# C-11_SOM_HDR.net
KiCad netlist of a schematic drawn in Altium Designer
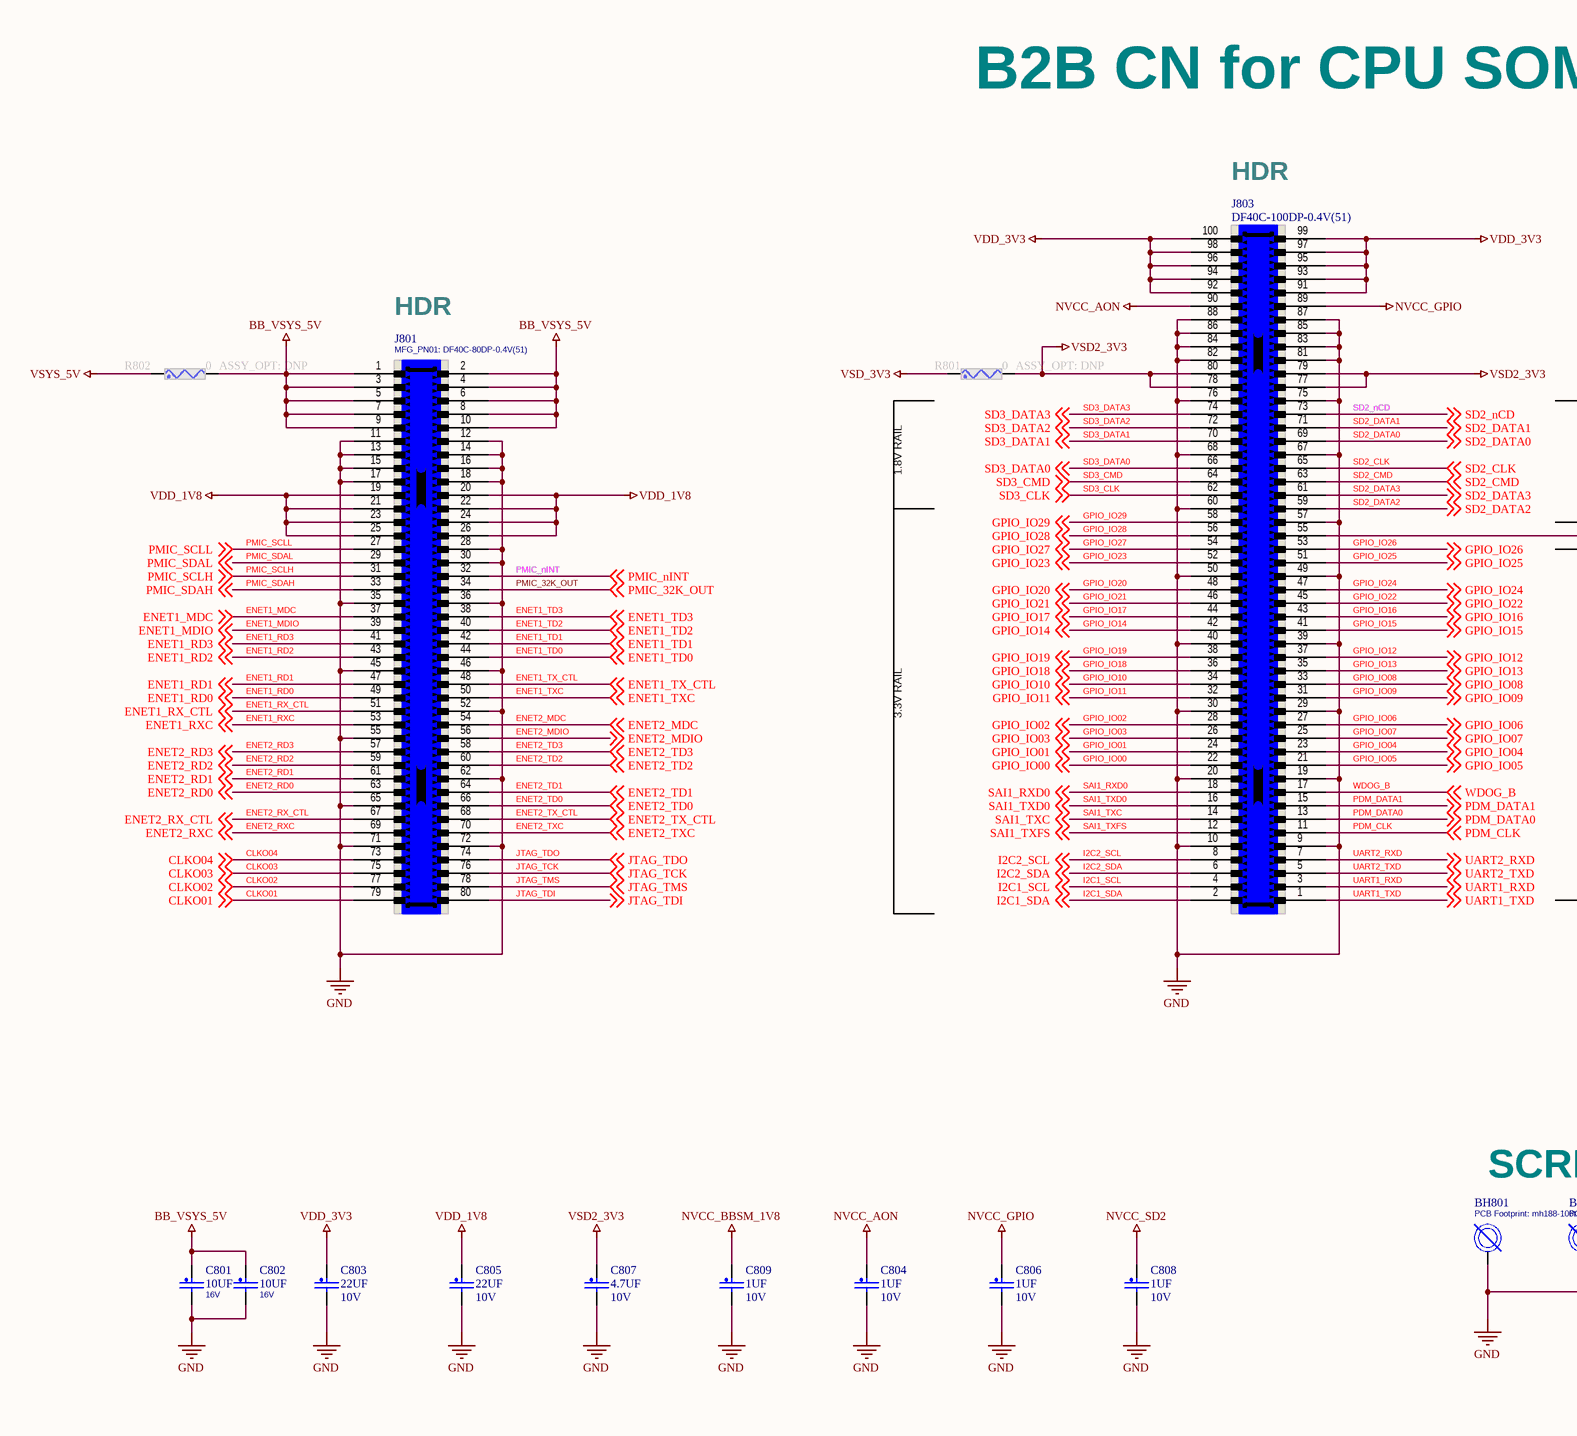
[diagram p0: C-11 SOM HDR.SchDoc, left]
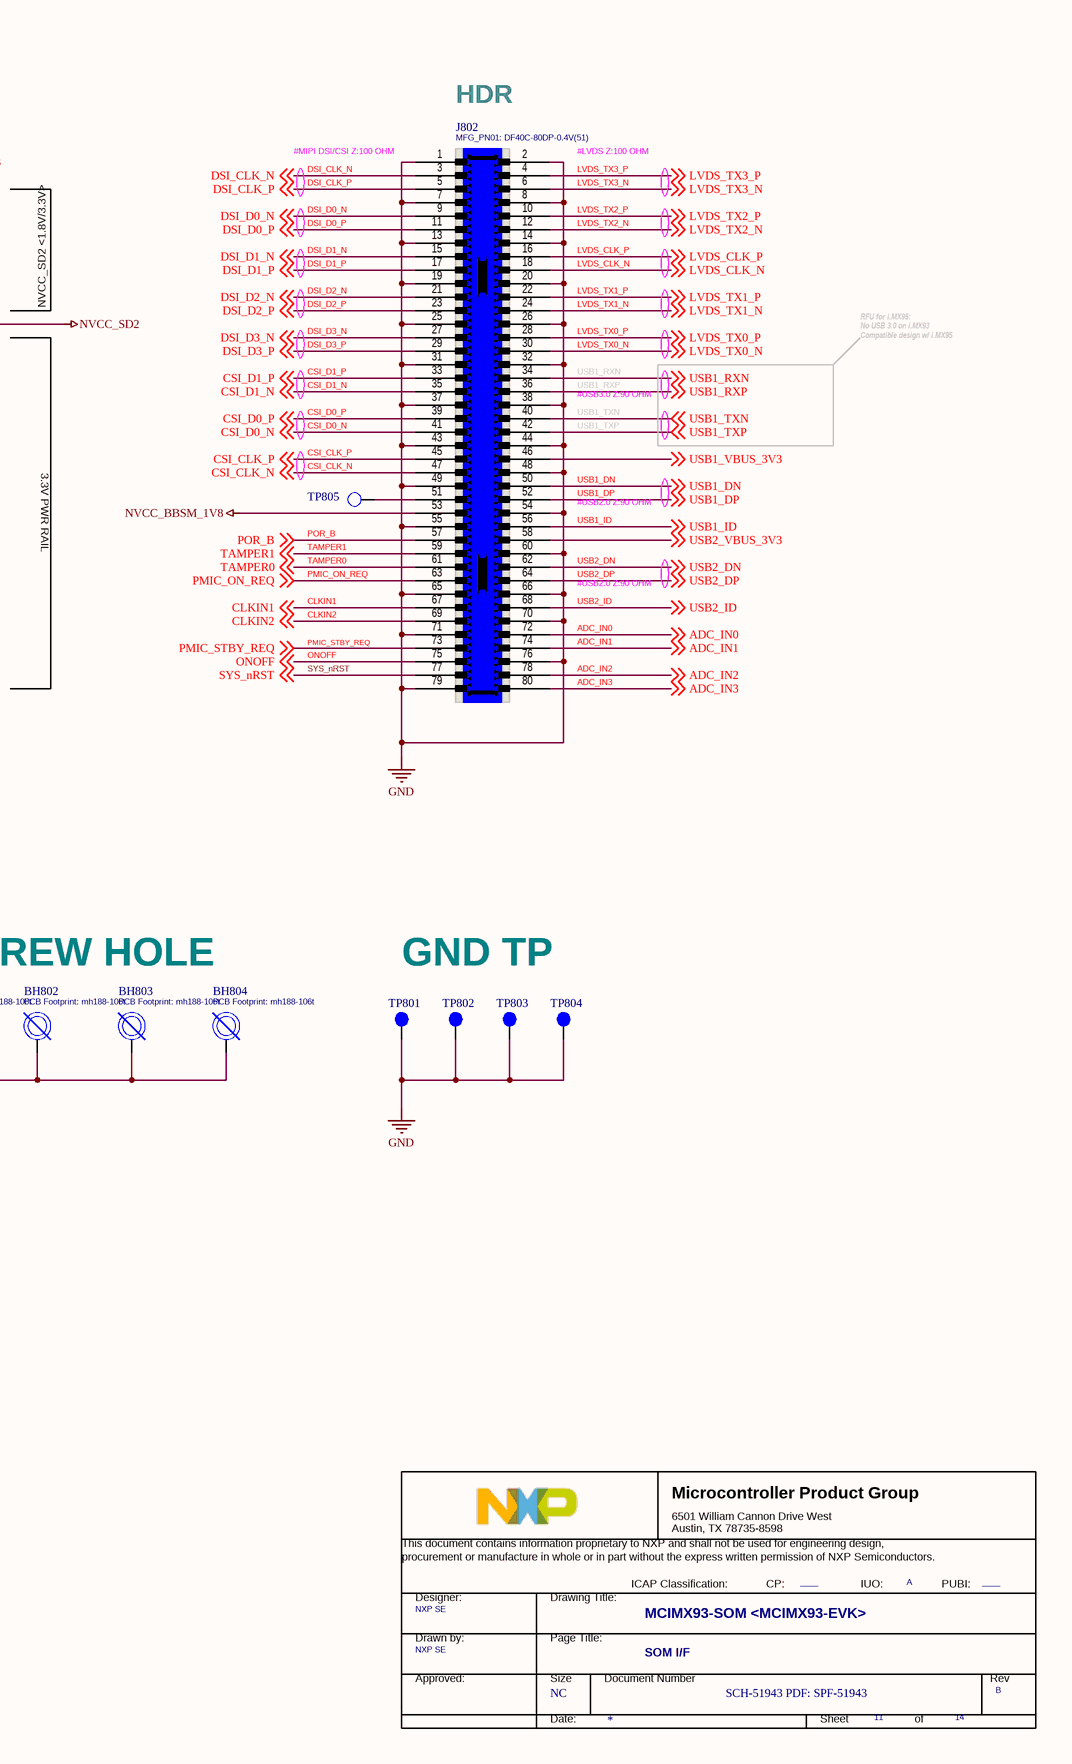
[diagram p1: C-11 SOM HDR.SchDoc, right]

(export (version "E")
  (design (tool "Eeschema 10.0.6"))
  (components
    (comp (ref "BH801")
      (value "FMC MOUNTING HOLE")
      (footprint "mh188-106t")
      (description "MOUNTING HOLE PLATED DRILL 2.7MM KEEPOUT R2.9MM TH, NO PART TO ORDER")
      (fields (field (name "PCB FOOTPRINT") "mh188-106t"))
      (libsource (lib "*") (part "MOUNT_HOLE"))
    )
    (comp (ref "BH802")
      (value "FMC MOUNTING HOLE")
      (footprint "mh188-106t")
      (description "MOUNTING HOLE PLATED DRILL 2.7MM KEEPOUT R2.9MM TH, NO PART TO ORDER")
      (fields (field (name "PCB FOOTPRINT") "mh188-106t"))
      (libsource (lib "*") (part "MOUNT_HOLE"))
    )
    (comp (ref "BH803")
      (value "FMC MOUNTING HOLE")
      (footprint "mh188-106t")
      (description "MOUNTING HOLE PLATED DRILL 2.7MM KEEPOUT R2.9MM TH, NO PART TO ORDER")
      (fields (field (name "PCB FOOTPRINT") "mh188-106t"))
      (libsource (lib "*") (part "MOUNT_HOLE"))
    )
    (comp (ref "BH804")
      (value "FMC MOUNTING HOLE")
      (footprint "mh188-106t")
      (description "MOUNTING HOLE PLATED DRILL 2.7MM KEEPOUT R2.9MM TH, NO PART TO ORDER")
      (fields (field (name "PCB FOOTPRINT") "mh188-106t"))
      (libsource (lib "*") (part "MOUNT_HOLE"))
    )
    (comp (ref "C801")
      (value "10UF")
      (footprint "CC0603")
      (description "CAP CER 10.0uF 16V 10% X5R 0603")
      (fields (field (name "TOLERANCE") "10%") (field (name "VOLTAGE") "16V"))
      (libsource (lib "*") (part "CAP_NP"))
    )
    (comp (ref "C802")
      (value "10UF")
      (footprint "CC0603")
      (description "CAP CER 10.0uF 16V 10% X5R 0603")
      (fields (field (name "VOLTAGE") "16V") (field (name "TOLERANCE") "10%"))
      (libsource (lib "*") (part "CAP_NP"))
    )
    (comp (ref "C803")
      (value "22UF")
      (footprint "CC0603")
      (description "CAP CER 22uF 10V 20% X5R 0603")
      (fields (field (name "TOLERANCE") "20%") (field (name "VOLTAGE") "10V"))
      (libsource (lib "*") (part "CAP_NP"))
    )
    (comp (ref "C804")
      (value "1UF")
      (footprint "0201_CC")
      (description "CAP CER 1.0uF 10V 10% X5R 0201")
      (fields (field (name "TOLERANCE") "10%") (field (name "VOLTAGE") "10V"))
      (libsource (lib "*") (part "CAP_NP"))
    )
    (comp (ref "C805")
      (value "22UF")
      (footprint "CC0603")
      (description "CAP CER 22uF 10V 20% X5R 0603")
      (fields (field (name "TOLERANCE") "20%") (field (name "VOLTAGE") "10V"))
      (libsource (lib "*") (part "CAP_NP"))
    )
    (comp (ref "C806")
      (value "1UF")
      (footprint "0201_CC")
      (description "CAP CER 1.0uF 10V 10% X5R 0201")
      (fields (field (name "TOLERANCE") "10%") (field (name "VOLTAGE") "10V"))
      (libsource (lib "*") (part "CAP_NP"))
    )
    (comp (ref "C807")
      (value "4.7UF")
      (footprint "cc0402_tol0p15")
      (description "CAP CER 4.7uF 10V 10% X5R 0402")
      (fields (field (name "VOLTAGE") "10V") (field (name "TOLERANCE") "10%"))
      (libsource (lib "*") (part "CAP_NP"))
    )
    (comp (ref "C808")
      (value "1UF")
      (footprint "0201_CC")
      (description "CAP CER 1.0uF 10V 10% X5R 0201")
      (fields (field (name "VOLTAGE") "10V") (field (name "TOLERANCE") "10%"))
      (libsource (lib "*") (part "CAP_NP"))
    )
    (comp (ref "C809")
      (value "1UF")
      (footprint "0201_CC")
      (description "CAP CER 1.0uF 10V 10% X5R 0201")
      (fields (field (name "TOLERANCE") "10%") (field (name "VOLTAGE") "10V"))
      (libsource (lib "*") (part "CAP_NP"))
    )
    (comp (ref "J801")
      (value "CON 2X40")
      (footprint "con80_0p4_17p7x2p05_sm")
      (description "CON 2X40 PLUG SHRD SMT 0.4MM SP 51H AU")
      (fields (field (name "MFG_PN01") "DF40C-80DP-0.4V(51)"))
      (libsource (lib "*") (part "CON_2X40_A"))
    )
    (comp (ref "J802")
      (value "CON 2X40")
      (footprint "con80_0p4_17p7x2p05_sm")
      (description "CON 2X40 PLUG SHRD SMT 0.4MM SP 51H AU")
      (fields (field (name "MFG_PN01") "DF40C-80DP-0.4V(51)"))
      (libsource (lib "*") (part "CON_2X40_A"))
    )
    (comp (ref "J803")
      (value "DF40C-100DP-0.4V(51)")
      (footprint "con100_0p4_21p7x2p05_sm")
      (description "CON 2X50 PLUG SHRD SMT 0.4MM SP 51H AU")
      (libsource (lib "*") (part "HDR_2X50_M_A"))
    )
    (comp (ref "R801")
      (value "0")
      (footprint "0603_CC")
      (description "RES MF ZERO OHM 1/10W -- 0603")
      (fields (field (name "ASSY_OPT") "DNP"))
      (libsource (lib "*") (part "RES"))
    )
    (comp (ref "R802")
      (value "0")
      (footprint "RC0805_OV")
      (description "RES MF ZERO OHM 1/8W -- 0805")
      (fields (field (name "ASSY_OPT") "DNP") (field (name "TOLERANCE") "5%"))
      (libsource (lib "*") (part "RES"))
    )
    (comp (ref "TP801")
      (value "TPAD_050")
      (footprint "TPAD_050")
      (description "TEST POINT PAD 50MIL DIA SMT, NO PART TO ORDER")
      (libsource (lib "*") (part "TESTLOOP"))
    )
    (comp (ref "TP802")
      (value "TPAD_050")
      (footprint "TPAD_050")
      (description "TEST POINT PAD 50MIL DIA SMT, NO PART TO ORDER")
      (libsource (lib "*") (part "TESTLOOP"))
    )
    (comp (ref "TP803")
      (value "TPAD_050")
      (footprint "TPAD_050")
      (description "TEST POINT PAD 50MIL DIA SMT, NO PART TO ORDER")
      (libsource (lib "*") (part "TESTLOOP"))
    )
    (comp (ref "TP804")
      (value "TPAD_050")
      (footprint "TPAD_050")
      (description "TEST POINT PAD 50MIL DIA SMT, NO PART TO ORDER")
      (libsource (lib "*") (part "TESTLOOP"))
    )
    (comp (ref "TP805")
      (value "TP_35MIL")
      (footprint "testpoint_35mil")
      (description "TEST POINT PAD .035 SMT, no part to order")
      (libsource (lib "*") (part "T POINT R"))
    )
  )
  (nets
    (net (code "1") (name "ADC_IN0") (class "Default")
      (node (ref "J802") (pin "72") (pinfunction "B36_72") (pintype "passive"))
    )
    (net (code "2") (name "ADC_IN1") (class "Default")
      (node (ref "J802") (pin "74") (pinfunction "B37_74") (pintype "passive"))
    )
    (net (code "3") (name "ADC_IN2") (class "Default")
      (node (ref "J802") (pin "78") (pinfunction "B39_78") (pintype "passive"))
    )
    (net (code "4") (name "ADC_IN3") (class "Default")
      (node (ref "J802") (pin "80") (pinfunction "B40_80") (pintype "passive"))
    )
    (net (code "5") (name "BB_VSYS_5V") (class "Default")
      (node (ref "C801") (pin "1") (pinfunction "1_1") (pintype "passive"))
      (node (ref "C802") (pin "1") (pinfunction "1_1") (pintype "passive"))
      (node (ref "J801") (pin "1") (pinfunction "A1_1") (pintype "passive"))
      (node (ref "J801") (pin "10") (pinfunction "B5_10") (pintype "passive"))
      (node (ref "J801") (pin "2") (pinfunction "B1_2") (pintype "passive"))
      (node (ref "J801") (pin "3") (pinfunction "A2_3") (pintype "passive"))
      (node (ref "J801") (pin "4") (pinfunction "B2_4") (pintype "passive"))
      (node (ref "J801") (pin "5") (pinfunction "A3_5") (pintype "passive"))
      (node (ref "J801") (pin "6") (pinfunction "B3_6") (pintype "passive"))
      (node (ref "J801") (pin "7") (pinfunction "A4_7") (pintype "passive"))
      (node (ref "J801") (pin "8") (pinfunction "B4_8") (pintype "passive"))
      (node (ref "J801") (pin "9") (pinfunction "A5_9") (pintype "passive"))
      (node (ref "R802") (pin "2") (pinfunction "2_2") (pintype "passive"))
    )
    (net (code "6") (name "CLKIN1") (class "Default")
      (node (ref "J802") (pin "67") (pinfunction "A34_67") (pintype "passive"))
    )
    (net (code "7") (name "CLKIN2") (class "Default")
      (node (ref "J802") (pin "69") (pinfunction "A35_69") (pintype "passive"))
    )
    (net (code "8") (name "CLKO01") (class "Default")
      (node (ref "J801") (pin "79") (pinfunction "A40_79") (pintype "passive"))
    )
    (net (code "9") (name "CLKO02") (class "Default")
      (node (ref "J801") (pin "77") (pinfunction "A39_77") (pintype "passive"))
    )
    (net (code "10") (name "CLKO03") (class "Default")
      (node (ref "J801") (pin "75") (pinfunction "A38_75") (pintype "passive"))
    )
    (net (code "11") (name "CLKO04") (class "Default")
      (node (ref "J801") (pin "73") (pinfunction "A37_73") (pintype "passive"))
    )
    (net (code "12") (name "CSI_CLK_N") (class "Default")
      (node (ref "J802") (pin "47") (pinfunction "A24_47") (pintype "passive"))
    )
    (net (code "13") (name "CSI_CLK_P") (class "Default")
      (node (ref "J802") (pin "45") (pinfunction "A23_45") (pintype "passive"))
    )
    (net (code "14") (name "CSI_D0_N") (class "Default")
      (node (ref "J802") (pin "41") (pinfunction "A21_41") (pintype "passive"))
    )
    (net (code "15") (name "CSI_D0_P") (class "Default")
      (node (ref "J802") (pin "39") (pinfunction "A20_39") (pintype "passive"))
    )
    (net (code "16") (name "CSI_D1_N") (class "Default")
      (node (ref "J802") (pin "35") (pinfunction "A18_35") (pintype "passive"))
    )
    (net (code "17") (name "CSI_D1_P") (class "Default")
      (node (ref "J802") (pin "33") (pinfunction "A17_33") (pintype "passive"))
    )
    (net (code "18") (name "DSI_CLK_N") (class "Default")
      (node (ref "J802") (pin "3") (pinfunction "A2_3") (pintype "passive"))
    )
    (net (code "19") (name "DSI_CLK_P") (class "Default")
      (node (ref "J802") (pin "5") (pinfunction "A3_5") (pintype "passive"))
    )
    (net (code "20") (name "DSI_D0_N") (class "Default")
      (node (ref "J802") (pin "9") (pinfunction "A5_9") (pintype "passive"))
    )
    (net (code "21") (name "DSI_D0_P") (class "Default")
      (node (ref "J802") (pin "11") (pinfunction "A6_11") (pintype "passive"))
    )
    (net (code "22") (name "DSI_D1_N") (class "Default")
      (node (ref "J802") (pin "15") (pinfunction "A8_15") (pintype "passive"))
    )
    (net (code "23") (name "DSI_D1_P") (class "Default")
      (node (ref "J802") (pin "17") (pinfunction "A9_17") (pintype "passive"))
    )
    (net (code "24") (name "DSI_D2_N") (class "Default")
      (node (ref "J802") (pin "21") (pinfunction "A11_21") (pintype "passive"))
    )
    (net (code "25") (name "DSI_D2_P") (class "Default")
      (node (ref "J802") (pin "23") (pinfunction "A12_23") (pintype "passive"))
    )
    (net (code "26") (name "DSI_D3_N") (class "Default")
      (node (ref "J802") (pin "27") (pinfunction "A14_27") (pintype "passive"))
    )
    (net (code "27") (name "DSI_D3_P") (class "Default")
      (node (ref "J802") (pin "29") (pinfunction "A15_29") (pintype "passive"))
    )
    (net (code "28") (name "ENET1_MDC") (class "Default")
      (node (ref "J801") (pin "37") (pinfunction "A19_37") (pintype "passive"))
    )
    (net (code "29") (name "ENET1_MDIO") (class "Default")
      (node (ref "J801") (pin "39") (pinfunction "A20_39") (pintype "passive"))
    )
    (net (code "30") (name "ENET1_RD0") (class "Default")
      (node (ref "J801") (pin "49") (pinfunction "A25_49") (pintype "passive"))
    )
    (net (code "31") (name "ENET1_RD1") (class "Default")
      (node (ref "J801") (pin "47") (pinfunction "A24_47") (pintype "passive"))
    )
    (net (code "32") (name "ENET1_RD2") (class "Default")
      (node (ref "J801") (pin "43") (pinfunction "A22_43") (pintype "passive"))
    )
    (net (code "33") (name "ENET1_RD3") (class "Default")
      (node (ref "J801") (pin "41") (pinfunction "A21_41") (pintype "passive"))
    )
    (net (code "34") (name "ENET1_RXC") (class "Default")
      (node (ref "J801") (pin "53") (pinfunction "A27_53") (pintype "passive"))
    )
    (net (code "35") (name "ENET1_RX_CTL") (class "Default")
      (node (ref "J801") (pin "51") (pinfunction "A26_51") (pintype "passive"))
    )
    (net (code "36") (name "ENET1_TD0") (class "Default")
      (node (ref "J801") (pin "44") (pinfunction "B22_44") (pintype "passive"))
    )
    (net (code "37") (name "ENET1_TD1") (class "Default")
      (node (ref "J801") (pin "42") (pinfunction "B21_42") (pintype "passive"))
    )
    (net (code "38") (name "ENET1_TD2") (class "Default")
      (node (ref "J801") (pin "40") (pinfunction "B20_40") (pintype "passive"))
    )
    (net (code "39") (name "ENET1_TD3") (class "Default")
      (node (ref "J801") (pin "38") (pinfunction "B19_38") (pintype "passive"))
    )
    (net (code "40") (name "ENET1_TXC") (class "Default")
      (node (ref "J801") (pin "50") (pinfunction "B25_50") (pintype "passive"))
    )
    (net (code "41") (name "ENET1_TX_CTL") (class "Default")
      (node (ref "J801") (pin "48") (pinfunction "B24_48") (pintype "passive"))
    )
    (net (code "42") (name "ENET2_MDC") (class "Default")
      (node (ref "J801") (pin "54") (pinfunction "B27_54") (pintype "passive"))
    )
    (net (code "43") (name "ENET2_MDIO") (class "Default")
      (node (ref "J801") (pin "56") (pinfunction "B28_56") (pintype "passive"))
    )
    (net (code "44") (name "ENET2_RD0") (class "Default")
      (node (ref "J801") (pin "63") (pinfunction "A32_63") (pintype "passive"))
    )
    (net (code "45") (name "ENET2_RD1") (class "Default")
      (node (ref "J801") (pin "61") (pinfunction "A31_61") (pintype "passive"))
    )
    (net (code "46") (name "ENET2_RD2") (class "Default")
      (node (ref "J801") (pin "59") (pinfunction "A30_59") (pintype "passive"))
    )
    (net (code "47") (name "ENET2_RD3") (class "Default")
      (node (ref "J801") (pin "57") (pinfunction "A29_57") (pintype "passive"))
    )
    (net (code "48") (name "ENET2_RXC") (class "Default")
      (node (ref "J801") (pin "69") (pinfunction "A35_69") (pintype "passive"))
    )
    (net (code "49") (name "ENET2_RX_CTL") (class "Default")
      (node (ref "J801") (pin "67") (pinfunction "A34_67") (pintype "passive"))
    )
    (net (code "50") (name "ENET2_TD0") (class "Default")
      (node (ref "J801") (pin "66") (pinfunction "B33_66") (pintype "passive"))
    )
    (net (code "51") (name "ENET2_TD1") (class "Default")
      (node (ref "J801") (pin "64") (pinfunction "B32_64") (pintype "passive"))
    )
    (net (code "52") (name "ENET2_TD2") (class "Default")
      (node (ref "J801") (pin "60") (pinfunction "B30_60") (pintype "passive"))
    )
    (net (code "53") (name "ENET2_TD3") (class "Default")
      (node (ref "J801") (pin "58") (pinfunction "B29_58") (pintype "passive"))
    )
    (net (code "54") (name "ENET2_TXC") (class "Default")
      (node (ref "J801") (pin "70") (pinfunction "B35_70") (pintype "passive"))
    )
    (net (code "55") (name "ENET2_TX_CTL") (class "Default")
      (node (ref "J801") (pin "68") (pinfunction "B34_68") (pintype "passive"))
    )
    (net (code "56") (name "GND") (class "Default")
      (node (ref "BH801") (pin "1") (pinfunction "1_1") (pintype "passive"))
      (node (ref "BH802") (pin "1") (pinfunction "1_1") (pintype "passive"))
      (node (ref "BH803") (pin "1") (pinfunction "1_1") (pintype "passive"))
      (node (ref "BH804") (pin "1") (pinfunction "1_1") (pintype "passive"))
      (node (ref "C801") (pin "2") (pinfunction "2_2") (pintype "passive"))
      (node (ref "C802") (pin "2") (pinfunction "2_2") (pintype "passive"))
      (node (ref "C803") (pin "2") (pinfunction "2_2") (pintype "passive"))
      (node (ref "C804") (pin "2") (pinfunction "2_2") (pintype "passive"))
      (node (ref "C805") (pin "2") (pinfunction "2_2") (pintype "passive"))
      (node (ref "C806") (pin "2") (pinfunction "2_2") (pintype "passive"))
      (node (ref "C807") (pin "2") (pinfunction "2_2") (pintype "passive"))
      (node (ref "C808") (pin "2") (pinfunction "2_2") (pintype "passive"))
      (node (ref "C809") (pin "2") (pinfunction "2_2") (pintype "passive"))
      (node (ref "J801") (pin "11") (pinfunction "A6_11") (pintype "passive"))
      (node (ref "J801") (pin "12") (pinfunction "B6_12") (pintype "passive"))
      (node (ref "J801") (pin "13") (pinfunction "A7_13") (pintype "passive"))
      (node (ref "J801") (pin "14") (pinfunction "B7_14") (pintype "passive"))
      (node (ref "J801") (pin "15") (pinfunction "A8_15") (pintype "passive"))
      (node (ref "J801") (pin "16") (pinfunction "B8_16") (pintype "passive"))
      (node (ref "J801") (pin "17") (pinfunction "A9_17") (pintype "passive"))
      (node (ref "J801") (pin "18") (pinfunction "B9_18") (pintype "passive"))
      (node (ref "J801") (pin "28") (pinfunction "B14_28") (pintype "passive"))
      (node (ref "J801") (pin "30") (pinfunction "B15_30") (pintype "passive"))
      (node (ref "J801") (pin "35") (pinfunction "A18_35") (pintype "passive"))
      (node (ref "J801") (pin "36") (pinfunction "B18_36") (pintype "passive"))
      (node (ref "J801") (pin "45") (pinfunction "A23_45") (pintype "passive"))
      (node (ref "J801") (pin "46") (pinfunction "B23_46") (pintype "passive"))
      (node (ref "J801") (pin "52") (pinfunction "B26_52") (pintype "passive"))
      (node (ref "J801") (pin "55") (pinfunction "A28_55") (pintype "passive"))
      (node (ref "J801") (pin "62") (pinfunction "B31_62") (pintype "passive"))
      (node (ref "J801") (pin "65") (pinfunction "A33_65") (pintype "passive"))
      (node (ref "J801") (pin "71") (pinfunction "A36_71") (pintype "passive"))
      (node (ref "J801") (pin "72") (pinfunction "B36_72") (pintype "passive"))
      (node (ref "J802") (pin "1") (pinfunction "A1_1") (pintype "passive"))
      (node (ref "J802") (pin "13") (pinfunction "A7_13") (pintype "passive"))
      (node (ref "J802") (pin "14") (pinfunction "B7_14") (pintype "passive"))
      (node (ref "J802") (pin "19") (pinfunction "A10_19") (pintype "passive"))
      (node (ref "J802") (pin "2") (pinfunction "B1_2") (pintype "passive"))
      (node (ref "J802") (pin "20") (pinfunction "B10_20") (pintype "passive"))
      (node (ref "J802") (pin "25") (pinfunction "A13_25") (pintype "passive"))
      (node (ref "J802") (pin "26") (pinfunction "B13_26") (pintype "passive"))
      (node (ref "J802") (pin "31") (pinfunction "A16_31") (pintype "passive"))
      (node (ref "J802") (pin "32") (pinfunction "B16_32") (pintype "passive"))
      (node (ref "J802") (pin "37") (pinfunction "A19_37") (pintype "passive"))
      (node (ref "J802") (pin "38") (pinfunction "B19_38") (pintype "passive"))
      (node (ref "J802") (pin "43") (pinfunction "A22_43") (pintype "passive"))
      (node (ref "J802") (pin "44") (pinfunction "B22_44") (pintype "passive"))
      (node (ref "J802") (pin "48") (pinfunction "B24_48") (pintype "passive"))
      (node (ref "J802") (pin "49") (pinfunction "A25_49") (pintype "passive"))
      (node (ref "J802") (pin "54") (pinfunction "B27_54") (pintype "passive"))
      (node (ref "J802") (pin "55") (pinfunction "A28_55") (pintype "passive"))
      (node (ref "J802") (pin "60") (pinfunction "B30_60") (pintype "passive"))
      (node (ref "J802") (pin "65") (pinfunction "A33_65") (pintype "passive"))
      (node (ref "J802") (pin "66") (pinfunction "B33_66") (pintype "passive"))
      (node (ref "J802") (pin "7") (pinfunction "A4_7") (pintype "passive"))
      (node (ref "J802") (pin "70") (pinfunction "B35_70") (pintype "passive"))
      (node (ref "J802") (pin "71") (pinfunction "A36_71") (pintype "passive"))
      (node (ref "J802") (pin "76") (pinfunction "B38_76") (pintype "passive"))
      (node (ref "J802") (pin "79") (pinfunction "A40_79") (pintype "passive"))
      (node (ref "J802") (pin "8") (pinfunction "B4_8") (pintype "passive"))
      (node (ref "J803") (pin "10") (pinfunction "10_10") (pintype "passive"))
      (node (ref "J803") (pin "19") (pinfunction "19_19") (pintype "passive"))
      (node (ref "J803") (pin "20") (pinfunction "20_20") (pintype "passive"))
      (node (ref "J803") (pin "29") (pinfunction "29_29") (pintype "passive"))
      (node (ref "J803") (pin "30") (pinfunction "30_30") (pintype "passive"))
      (node (ref "J803") (pin "39") (pinfunction "39_39") (pintype "passive"))
      (node (ref "J803") (pin "40") (pinfunction "40_40") (pintype "passive"))
      (node (ref "J803") (pin "49") (pinfunction "49_49") (pintype "passive"))
      (node (ref "J803") (pin "50") (pinfunction "50_50") (pintype "passive"))
      (node (ref "J803") (pin "57") (pinfunction "57_57") (pintype "passive"))
      (node (ref "J803") (pin "60") (pinfunction "60_60") (pintype "passive"))
      (node (ref "J803") (pin "67") (pinfunction "67_67") (pintype "passive"))
      (node (ref "J803") (pin "68") (pinfunction "68_68") (pintype "passive"))
      (node (ref "J803") (pin "75") (pinfunction "75_75") (pintype "passive"))
      (node (ref "J803") (pin "76") (pinfunction "76_76") (pintype "passive"))
      (node (ref "J803") (pin "81") (pinfunction "81_81") (pintype "passive"))
      (node (ref "J803") (pin "82") (pinfunction "82_82") (pintype "passive"))
      (node (ref "J803") (pin "83") (pinfunction "83_83") (pintype "passive"))
      (node (ref "J803") (pin "84") (pinfunction "84_84") (pintype "passive"))
      (node (ref "J803") (pin "85") (pinfunction "85_85") (pintype "passive"))
      (node (ref "J803") (pin "86") (pinfunction "86_86") (pintype "passive"))
      (node (ref "J803") (pin "87") (pinfunction "87_87") (pintype "passive"))
      (node (ref "J803") (pin "88") (pinfunction "88_88") (pintype "passive"))
      (node (ref "J803") (pin "9") (pinfunction "9_9") (pintype "passive"))
      (node (ref "TP801") (pin "1") (pinfunction "Pin1_1") (pintype "passive"))
      (node (ref "TP802") (pin "1") (pinfunction "Pin1_1") (pintype "passive"))
      (node (ref "TP803") (pin "1") (pinfunction "Pin1_1") (pintype "passive"))
      (node (ref "TP804") (pin "1") (pinfunction "Pin1_1") (pintype "passive"))
    )
    (net (code "57") (name "GPIO_IO00") (class "Default")
      (node (ref "J803") (pin "22") (pinfunction "22_22") (pintype "passive"))
    )
    (net (code "58") (name "GPIO_IO01") (class "Default")
      (node (ref "J803") (pin "24") (pinfunction "24_24") (pintype "passive"))
    )
    (net (code "59") (name "GPIO_IO02") (class "Default")
      (node (ref "J803") (pin "28") (pinfunction "28_28") (pintype "passive"))
    )
    (net (code "60") (name "GPIO_IO03") (class "Default")
      (node (ref "J803") (pin "26") (pinfunction "26_26") (pintype "passive"))
    )
    (net (code "61") (name "GPIO_IO04") (class "Default")
      (node (ref "J803") (pin "23") (pinfunction "23_23") (pintype "passive"))
    )
    (net (code "62") (name "GPIO_IO05") (class "Default")
      (node (ref "J803") (pin "21") (pinfunction "21_21") (pintype "passive"))
    )
    (net (code "63") (name "GPIO_IO06") (class "Default")
      (node (ref "J803") (pin "27") (pinfunction "27_27") (pintype "passive"))
    )
    (net (code "64") (name "GPIO_IO07") (class "Default")
      (node (ref "J803") (pin "25") (pinfunction "25_25") (pintype "passive"))
    )
    (net (code "65") (name "GPIO_IO08") (class "Default")
      (node (ref "J803") (pin "33") (pinfunction "33_33") (pintype "passive"))
    )
    (net (code "66") (name "GPIO_IO09") (class "Default")
      (node (ref "J803") (pin "31") (pinfunction "31_31") (pintype "passive"))
    )
    (net (code "67") (name "GPIO_IO10") (class "Default")
      (node (ref "J803") (pin "34") (pinfunction "34_34") (pintype "passive"))
    )
    (net (code "68") (name "GPIO_IO11") (class "Default")
      (node (ref "J803") (pin "32") (pinfunction "32_32") (pintype "passive"))
    )
    (net (code "69") (name "GPIO_IO12") (class "Default")
      (node (ref "J803") (pin "37") (pinfunction "37_37") (pintype "passive"))
    )
    (net (code "70") (name "GPIO_IO13") (class "Default")
      (node (ref "J803") (pin "35") (pinfunction "35_35") (pintype "passive"))
    )
    (net (code "71") (name "GPIO_IO14") (class "Default")
      (node (ref "J803") (pin "42") (pinfunction "42_42") (pintype "passive"))
    )
    (net (code "72") (name "GPIO_IO15") (class "Default")
      (node (ref "J803") (pin "41") (pinfunction "41_41") (pintype "passive"))
    )
    (net (code "73") (name "GPIO_IO16") (class "Default")
      (node (ref "J803") (pin "43") (pinfunction "43_43") (pintype "passive"))
    )
    (net (code "74") (name "GPIO_IO17") (class "Default")
      (node (ref "J803") (pin "44") (pinfunction "44_44") (pintype "passive"))
    )
    (net (code "75") (name "GPIO_IO18") (class "Default")
      (node (ref "J803") (pin "36") (pinfunction "36_36") (pintype "passive"))
    )
    (net (code "76") (name "GPIO_IO19") (class "Default")
      (node (ref "J803") (pin "38") (pinfunction "38_38") (pintype "passive"))
    )
    (net (code "77") (name "GPIO_IO20") (class "Default")
      (node (ref "J803") (pin "48") (pinfunction "48_48") (pintype "passive"))
    )
    (net (code "78") (name "GPIO_IO21") (class "Default")
      (node (ref "J803") (pin "46") (pinfunction "46_46") (pintype "passive"))
    )
    (net (code "79") (name "GPIO_IO22") (class "Default")
      (node (ref "J803") (pin "45") (pinfunction "45_45") (pintype "passive"))
    )
    (net (code "80") (name "GPIO_IO23") (class "Default")
      (node (ref "J803") (pin "52") (pinfunction "52_52") (pintype "passive"))
    )
    (net (code "81") (name "GPIO_IO24") (class "Default")
      (node (ref "J803") (pin "47") (pinfunction "47_47") (pintype "passive"))
    )
    (net (code "82") (name "GPIO_IO25") (class "Default")
      (node (ref "J803") (pin "51") (pinfunction "51_51") (pintype "passive"))
    )
    (net (code "83") (name "GPIO_IO26") (class "Default")
      (node (ref "J803") (pin "53") (pinfunction "53_53") (pintype "passive"))
    )
    (net (code "84") (name "GPIO_IO27") (class "Default")
      (node (ref "J803") (pin "54") (pinfunction "54_54") (pintype "passive"))
    )
    (net (code "85") (name "GPIO_IO28") (class "Default")
      (node (ref "J803") (pin "56") (pinfunction "56_56") (pintype "passive"))
    )
    (net (code "86") (name "GPIO_IO29") (class "Default")
      (node (ref "J803") (pin "58") (pinfunction "58_58") (pintype "passive"))
    )
    (net (code "87") (name "I2C1_SCL") (class "Default")
      (node (ref "J803") (pin "4") (pinfunction "4_4") (pintype "passive"))
    )
    (net (code "88") (name "I2C1_SDA") (class "Default")
      (node (ref "J803") (pin "2") (pinfunction "2_2") (pintype "passive"))
    )
    (net (code "89") (name "I2C2_SCL") (class "Default")
      (node (ref "J803") (pin "8") (pinfunction "8_8") (pintype "passive"))
    )
    (net (code "90") (name "I2C2_SDA") (class "Default")
      (node (ref "J803") (pin "6") (pinfunction "6_6") (pintype "passive"))
    )
    (net (code "91") (name "JTAG_TCK") (class "Default")
      (node (ref "J801") (pin "76") (pinfunction "B38_76") (pintype "passive"))
    )
    (net (code "92") (name "JTAG_TDI") (class "Default")
      (node (ref "J801") (pin "80") (pinfunction "B40_80") (pintype "passive"))
    )
    (net (code "93") (name "JTAG_TDO") (class "Default")
      (node (ref "J801") (pin "74") (pinfunction "B37_74") (pintype "passive"))
    )
    (net (code "94") (name "JTAG_TMS") (class "Default")
      (node (ref "J801") (pin "78") (pinfunction "B39_78") (pintype "passive"))
    )
    (net (code "95") (name "LVDS_CLK_N") (class "Default")
      (node (ref "J802") (pin "18") (pinfunction "B9_18") (pintype "passive"))
    )
    (net (code "96") (name "LVDS_CLK_P") (class "Default")
      (node (ref "J802") (pin "16") (pinfunction "B8_16") (pintype "passive"))
    )
    (net (code "97") (name "LVDS_TX0_N") (class "Default")
      (node (ref "J802") (pin "30") (pinfunction "B15_30") (pintype "passive"))
    )
    (net (code "98") (name "LVDS_TX0_P") (class "Default")
      (node (ref "J802") (pin "28") (pinfunction "B14_28") (pintype "passive"))
    )
    (net (code "99") (name "LVDS_TX1_N") (class "Default")
      (node (ref "J802") (pin "24") (pinfunction "B12_24") (pintype "passive"))
    )
    (net (code "100") (name "LVDS_TX1_P") (class "Default")
      (node (ref "J802") (pin "22") (pinfunction "B11_22") (pintype "passive"))
    )
    (net (code "101") (name "LVDS_TX2_N") (class "Default")
      (node (ref "J802") (pin "12") (pinfunction "B6_12") (pintype "passive"))
    )
    (net (code "102") (name "LVDS_TX2_P") (class "Default")
      (node (ref "J802") (pin "10") (pinfunction "B5_10") (pintype "passive"))
    )
    (net (code "103") (name "LVDS_TX3_N") (class "Default")
      (node (ref "J802") (pin "6") (pinfunction "B3_6") (pintype "passive"))
    )
    (net (code "104") (name "LVDS_TX3_P") (class "Default")
      (node (ref "J802") (pin "4") (pinfunction "B2_4") (pintype "passive"))
    )
    (net (code "105") (name "NVCC_AON") (class "Default")
      (node (ref "C804") (pin "1") (pinfunction "1_1") (pintype "passive"))
      (node (ref "J803") (pin "90") (pinfunction "90_90") (pintype "passive"))
    )
    (net (code "106") (name "NVCC_BBSM_1V8") (class "Default")
      (node (ref "C809") (pin "1") (pinfunction "1_1") (pintype "passive"))
      (node (ref "J802") (pin "53") (pinfunction "A27_53") (pintype "passive"))
    )
    (net (code "107") (name "NVCC_GPIO") (class "Default")
      (node (ref "C806") (pin "1") (pinfunction "1_1") (pintype "passive"))
      (node (ref "J803") (pin "89") (pinfunction "89_89") (pintype "passive"))
    )
    (net (code "108") (name "NVCC_SD2") (class "Default")
      (node (ref "C808") (pin "1") (pinfunction "1_1") (pintype "passive"))
      (node (ref "J803") (pin "55") (pinfunction "55_55") (pintype "passive"))
    )
    (net (code "109") (name "Net-(J802-A26)") (class "Default")
      (node (ref "J802") (pin "51") (pinfunction "A26_51") (pintype "passive"))
      (node (ref "TP805") (pin "1") (pinfunction "TP_1") (pintype "passive"))
    )
    (net (code "110") (name "ONOFF") (class "Default")
      (node (ref "J802") (pin "75") (pinfunction "A38_75") (pintype "passive"))
    )
    (net (code "111") (name "PDM_CLK") (class "Default")
      (node (ref "J803") (pin "11") (pinfunction "11_11") (pintype "passive"))
    )
    (net (code "112") (name "PDM_DATA0") (class "Default")
      (node (ref "J803") (pin "13") (pinfunction "13_13") (pintype "passive"))
    )
    (net (code "113") (name "PDM_DATA1") (class "Default")
      (node (ref "J803") (pin "15") (pinfunction "15_15") (pintype "passive"))
    )
    (net (code "114") (name "PMIC_32K_OUT") (class "Default")
      (node (ref "J801") (pin "34") (pinfunction "B17_34") (pintype "passive"))
    )
    (net (code "115") (name "PMIC_ON_REQ") (class "Default")
      (node (ref "J802") (pin "63") (pinfunction "A32_63") (pintype "passive"))
    )
    (net (code "116") (name "PMIC_SCLH") (class "Default")
      (node (ref "J801") (pin "31") (pinfunction "A16_31") (pintype "passive"))
    )
    (net (code "117") (name "PMIC_SCLL") (class "Default")
      (node (ref "J801") (pin "27") (pinfunction "A14_27") (pintype "passive"))
    )
    (net (code "118") (name "PMIC_SDAH") (class "Default")
      (node (ref "J801") (pin "33") (pinfunction "A17_33") (pintype "passive"))
    )
    (net (code "119") (name "PMIC_SDAL") (class "Default")
      (node (ref "J801") (pin "29") (pinfunction "A15_29") (pintype "passive"))
    )
    (net (code "120") (name "PMIC_STBY_REQ") (class "Default")
      (node (ref "J802") (pin "73") (pinfunction "A37_73") (pintype "passive"))
    )
    (net (code "121") (name "PMIC_nINT") (class "Default")
      (node (ref "J801") (pin "32") (pinfunction "B16_32") (pintype "passive"))
    )
    (net (code "122") (name "POR_B") (class "Default")
      (node (ref "J802") (pin "57") (pinfunction "A29_57") (pintype "passive"))
    )
    (net (code "123") (name "SAI1_RXD0") (class "Default")
      (node (ref "J803") (pin "18") (pinfunction "18_18") (pintype "passive"))
    )
    (net (code "124") (name "SAI1_TXC") (class "Default")
      (node (ref "J803") (pin "14") (pinfunction "14_14") (pintype "passive"))
    )
    (net (code "125") (name "SAI1_TXD0") (class "Default")
      (node (ref "J803") (pin "16") (pinfunction "16_16") (pintype "passive"))
    )
    (net (code "126") (name "SAI1_TXFS") (class "Default")
      (node (ref "J803") (pin "12") (pinfunction "12_12") (pintype "passive"))
    )
    (net (code "127") (name "SD2_CLK") (class "Default")
      (node (ref "J803") (pin "65") (pinfunction "65_65") (pintype "passive"))
    )
    (net (code "128") (name "SD2_CMD") (class "Default")
      (node (ref "J803") (pin "63") (pinfunction "63_63") (pintype "passive"))
    )
    (net (code "129") (name "SD2_DATA0") (class "Default")
      (node (ref "J803") (pin "69") (pinfunction "69_69") (pintype "passive"))
    )
    (net (code "130") (name "SD2_DATA1") (class "Default")
      (node (ref "J803") (pin "71") (pinfunction "71_71") (pintype "passive"))
    )
    (net (code "131") (name "SD2_DATA2") (class "Default")
      (node (ref "J803") (pin "59") (pinfunction "59_59") (pintype "passive"))
    )
    (net (code "132") (name "SD2_DATA3") (class "Default")
      (node (ref "J803") (pin "61") (pinfunction "61_61") (pintype "passive"))
    )
    (net (code "133") (name "SD2_nCD") (class "Default")
      (node (ref "J803") (pin "73") (pinfunction "73_73") (pintype "passive"))
    )
    (net (code "134") (name "SD3_CLK") (class "Default")
      (node (ref "J803") (pin "62") (pinfunction "62_62") (pintype "passive"))
    )
    (net (code "135") (name "SD3_CMD") (class "Default")
      (node (ref "J803") (pin "64") (pinfunction "64_64") (pintype "passive"))
    )
    (net (code "136") (name "SD3_DATA0") (class "Default")
      (node (ref "J803") (pin "66") (pinfunction "66_66") (pintype "passive"))
    )
    (net (code "137") (name "SD3_DATA1") (class "Default")
      (node (ref "J803") (pin "70") (pinfunction "70_70") (pintype "passive"))
    )
    (net (code "138") (name "SD3_DATA2") (class "Default")
      (node (ref "J803") (pin "72") (pinfunction "72_72") (pintype "passive"))
    )
    (net (code "139") (name "SD3_DATA3") (class "Default")
      (node (ref "J803") (pin "74") (pinfunction "74_74") (pintype "passive"))
    )
    (net (code "140") (name "SYS_nRST") (class "Default")
      (node (ref "J802") (pin "77") (pinfunction "A39_77") (pintype "passive"))
    )
    (net (code "141") (name "TAMPER0") (class "Default")
      (node (ref "J802") (pin "61") (pinfunction "A31_61") (pintype "passive"))
    )
    (net (code "142") (name "TAMPER1") (class "Default")
      (node (ref "J802") (pin "59") (pinfunction "A30_59") (pintype "passive"))
    )
    (net (code "143") (name "UART1_RXD") (class "Default")
      (node (ref "J803") (pin "3") (pinfunction "3_3") (pintype "passive"))
    )
    (net (code "144") (name "UART1_TXD") (class "Default")
      (node (ref "J803") (pin "1") (pinfunction "1_1") (pintype "passive"))
    )
    (net (code "145") (name "UART2_RXD") (class "Default")
      (node (ref "J803") (pin "7") (pinfunction "7_7") (pintype "passive"))
    )
    (net (code "146") (name "UART2_TXD") (class "Default")
      (node (ref "J803") (pin "5") (pinfunction "5_5") (pintype "passive"))
    )
    (net (code "147") (name "USB1_DN") (class "Default")
      (node (ref "J802") (pin "50") (pinfunction "B25_50") (pintype "passive"))
    )
    (net (code "148") (name "USB1_DP") (class "Default")
      (node (ref "J802") (pin "52") (pinfunction "B26_52") (pintype "passive"))
    )
    (net (code "149") (name "USB1_ID") (class "Default")
      (node (ref "J802") (pin "56") (pinfunction "B28_56") (pintype "passive"))
    )
    (net (code "150") (name "USB1_RXN") (class "Default")
      (node (ref "J802") (pin "34") (pinfunction "B17_34") (pintype "passive"))
    )
    (net (code "151") (name "USB1_RXP") (class "Default")
      (node (ref "J802") (pin "36") (pinfunction "B18_36") (pintype "passive"))
    )
    (net (code "152") (name "USB1_TXN") (class "Default")
      (node (ref "J802") (pin "40") (pinfunction "B20_40") (pintype "passive"))
    )
    (net (code "153") (name "USB1_TXP") (class "Default")
      (node (ref "J802") (pin "42") (pinfunction "B21_42") (pintype "passive"))
    )
    (net (code "154") (name "USB1_VBUS_3V3") (class "Default")
      (node (ref "J802") (pin "46") (pinfunction "B23_46") (pintype "passive"))
    )
    (net (code "155") (name "USB2_DN") (class "Default")
      (node (ref "J802") (pin "62") (pinfunction "B31_62") (pintype "passive"))
    )
    (net (code "156") (name "USB2_DP") (class "Default")
      (node (ref "J802") (pin "64") (pinfunction "B32_64") (pintype "passive"))
    )
    (net (code "157") (name "USB2_ID") (class "Default")
      (node (ref "J802") (pin "68") (pinfunction "B34_68") (pintype "passive"))
    )
    (net (code "158") (name "USB2_VBUS_3V3") (class "Default")
      (node (ref "J802") (pin "58") (pinfunction "B29_58") (pintype "passive"))
    )
    (net (code "159") (name "VDD_1V8") (class "Default")
      (node (ref "C805") (pin "1") (pinfunction "1_1") (pintype "passive"))
      (node (ref "J801") (pin "19") (pinfunction "A10_19") (pintype "passive"))
      (node (ref "J801") (pin "20") (pinfunction "B10_20") (pintype "passive"))
      (node (ref "J801") (pin "21") (pinfunction "A11_21") (pintype "passive"))
      (node (ref "J801") (pin "22") (pinfunction "B11_22") (pintype "passive"))
      (node (ref "J801") (pin "23") (pinfunction "A12_23") (pintype "passive"))
      (node (ref "J801") (pin "24") (pinfunction "B12_24") (pintype "passive"))
      (node (ref "J801") (pin "25") (pinfunction "A13_25") (pintype "passive"))
      (node (ref "J801") (pin "26") (pinfunction "B13_26") (pintype "passive"))
    )
    (net (code "160") (name "VDD_3V3") (class "Default")
      (node (ref "C803") (pin "1") (pinfunction "1_1") (pintype "passive"))
      (node (ref "J803") (pin "100") (pinfunction "100_100") (pintype "passive"))
      (node (ref "J803") (pin "91") (pinfunction "91_91") (pintype "passive"))
      (node (ref "J803") (pin "92") (pinfunction "92_92") (pintype "passive"))
      (node (ref "J803") (pin "93") (pinfunction "93_93") (pintype "passive"))
      (node (ref "J803") (pin "94") (pinfunction "94_94") (pintype "passive"))
      (node (ref "J803") (pin "95") (pinfunction "95_95") (pintype "passive"))
      (node (ref "J803") (pin "96") (pinfunction "96_96") (pintype "passive"))
      (node (ref "J803") (pin "97") (pinfunction "97_97") (pintype "passive"))
      (node (ref "J803") (pin "98") (pinfunction "98_98") (pintype "passive"))
      (node (ref "J803") (pin "99") (pinfunction "99_99") (pintype "passive"))
    )
    (net (code "161") (name "VSD2_3V3") (class "Default")
      (node (ref "C807") (pin "1") (pinfunction "1_1") (pintype "passive"))
      (node (ref "J803") (pin "77") (pinfunction "77_77") (pintype "passive"))
      (node (ref "J803") (pin "78") (pinfunction "78_78") (pintype "passive"))
      (node (ref "J803") (pin "79") (pinfunction "79_79") (pintype "passive"))
      (node (ref "J803") (pin "80") (pinfunction "80_80") (pintype "passive"))
      (node (ref "R801") (pin "2") (pinfunction "2_2") (pintype "passive"))
    )
    (net (code "162") (name "VSD_3V3") (class "Default")
      (node (ref "R801") (pin "1") (pinfunction "1_1") (pintype "passive"))
    )
    (net (code "163") (name "VSYS_5V") (class "Default")
      (node (ref "R802") (pin "1") (pinfunction "1_1") (pintype "passive"))
    )
    (net (code "164") (name "WDOG_B") (class "Default")
      (node (ref "J803") (pin "17") (pinfunction "17_17") (pintype "passive"))
    )
  )
)
